# DIO.net
KiCad netlist of a schematic drawn in Altium Designer
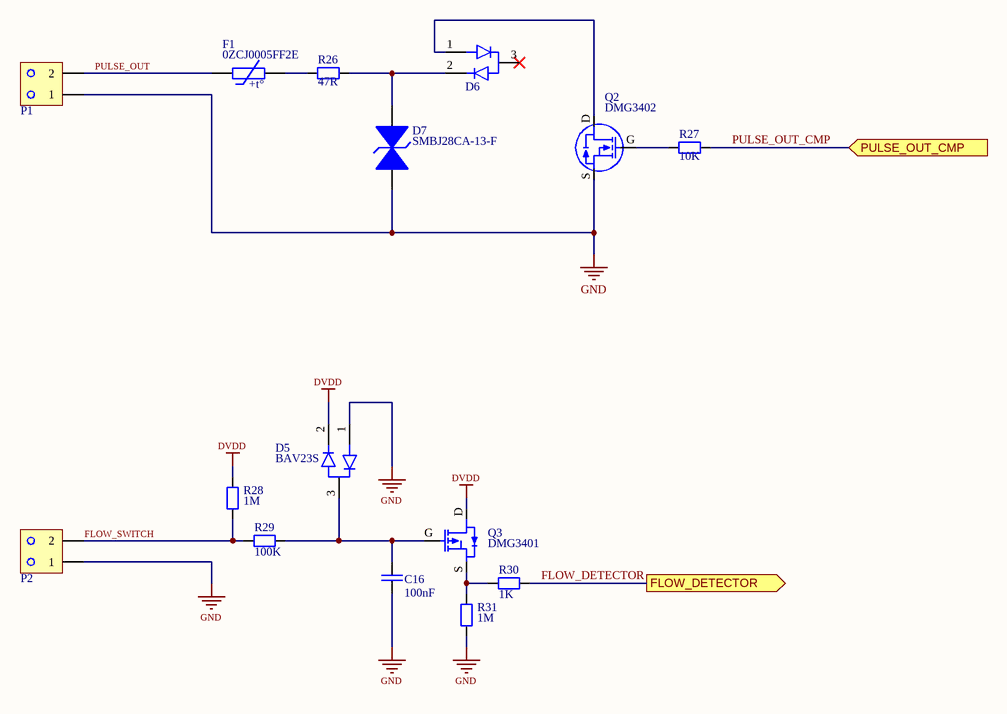
[diagram p0: DIO.SchDoc]

(export (version "E")
  (design (tool "Eeschema 10.0.6"))
  (components
    (comp (ref "C16")
      (value "100nF")
      (footprint "CAP_SM0805_YAGEOCC2_N")
      (description "CAP 100nF SM0805 X7R 25V YAGEO CC2")
      (fields
        (field (name "MANUFACTURER") "Yageo")
        (field (name "MANUFACTURER PART NUMBER") "CC0805KRX7R8BB104")
      )
      (libsource (lib "Yageo") (part "CC0805KRX7R8BB104"))
    )
    (comp (ref "D5")
      (value "BAV23S")
      (footprint "BAV23S")
      (description "DIODE ARRAY GP 250V 200MA SOT23")
      (fields (field (name "MANUFACTURER") "onsemi"))
      (libsource (lib "diode") (part "BAV23S"))
    )
    (comp (ref "D6")
      (value "BAV23S")
      (footprint "BAV23S")
      (description "DIODE ARRAY GP 250V 200MA SOT23")
      (fields (field (name "MANUFACTURER") "onsemi"))
      (libsource (lib "diode") (part "BAV23S"))
    )
    (comp (ref "D7")
      (value "SMBJ28CA-13-F")
      (footprint "SMBJ28CA-13-F")
      (fields
        (field (name "MANUFACTURER") "Diodes Incorporated")
        (field (name "MANUFACTURER PART NUMBER") "SMBJ24CA")
      )
      (libsource (lib "diode") (part "SMBJ28CA-13-F"))
    )
    (comp (ref "F1")
      (value "0ZCJ0005FF2E")
      (footprint "0ZCJ0005FF2E")
      (description "PTC RESET FUSE 60V 50MA 1206")
      (fields (field (name "MANUFACTURER") "Bel Fuse Inc."))
      (libsource (lib "fuse") (part "0ZCJ0005FF2E"))
    )
    (comp (ref "P1")
      (value "WJ15EDGVC-3.81-2P")
      (footprint "HEADER PLUG 2")
      (description "TERM BLOK FEMALE 1X2 3.81MM")
      (fields (field (name "MANUFACTURER") "Ningbo Kangnex Elec"))
      (libsource (lib "plug") (part "WJ15EDGVC-3.81-2P"))
    )
    (comp (ref "P2")
      (value "WJ15EDGVC-3.81-2P")
      (footprint "HEADER PLUG 2")
      (description "TERM BLOK FEMALE 1X2 3.81MM")
      (fields (field (name "MANUFACTURER") "Ningbo Kangnex Elec"))
      (libsource (lib "plug") (part "WJ15EDGVC-3.81-2P"))
    )
    (comp (ref "Q2")
      (value "DMG3402")
      (footprint "DMG3402L-7")
      (description "N-CHANNEL ENHANCEMENT MODE FIELD EFFECT TRANSISTOR\r\n85mΩ @ VGS = 2.5V -> ID 2A\r\nV(BR)DDS 30V")
      (fields
        (field (name "MANUFACTURER") "Diodes Incorporated")
        (field (name "MANUFACTURER PART NUMBER") "DMG3402L-7")
      )
      (libsource (lib "mosfet") (part "DMG3402L-7"))
    )
    (comp (ref "Q3")
      (value "DMG3401")
      (footprint "DMG3401LSN-7")
      (description "P-CHANNEL ENHANCEMENT MODE MOSFET\r\nRDS(ON) = 85mΩ @ VGS = -2.5V -> ID -2.7A\r\nV(BR)DDS 30V")
      (fields
        (field (name "MANUFACTURER") "Diodes Incorporated")
        (field (name "MANUFACTURER PART NUMBER") "DMG3401LSN-7")
      )
      (libsource (lib "mosfet") (part "DMG3401LSN-7"))
    )
    (comp (ref "R26")
      (value "47R")
      (footprint "RES_SM0805_YAGEORC_N")
      (description "RES 47R SM0805 YAGEO RC_L")
      (fields
        (field (name "MANUFACTURER") "Yageo")
        (field (name "MANUFACTURER PART NUMBER") "RC0805FR-0747RL")
      )
      (libsource (lib "Yageo") (part "RC0805FR-0747RL"))
    )
    (comp (ref "R27")
      (value "10K")
      (footprint "RES_SM0805_YAGEORC_N")
      (description "RES 10K SM0805 YAGEO RC_L")
      (fields
        (field (name "MANUFACTURER") "Yageo")
        (field (name "MANUFACTURER PART NUMBER") "RC0805FR-0710KL")
      )
      (libsource (lib "Yageo") (part "RC0805FR-0710KL"))
    )
    (comp (ref "R28")
      (value "1M")
      (footprint "RES_SM0805_YAGEORC_N")
      (description "RES 1M SM0805 YAGEO RC_L")
      (fields
        (field (name "MANUFACTURER") "Yageo")
        (field (name "MANUFACTURER PART NUMBER") "RC0805FR-071ML")
      )
      (libsource (lib "Yageo") (part "RC0805FR-071ML"))
    )
    (comp (ref "R29")
      (value "100K")
      (footprint "RES_SM0805_YAGEORC_N")
      (description "RES 100K SM0805 YAGEO RC_L")
      (fields
        (field (name "MANUFACTURER") "Yageo")
        (field (name "MANUFACTURER PART NUMBER") "RC0805FR-07100KL")
      )
      (libsource (lib "Yageo") (part "RC0805FR-07100KL"))
    )
    (comp (ref "R30")
      (value "1K")
      (footprint "RES_SM0805_YAGEORC_N")
      (description "RES 1K SM0805 YAGEO RC_L")
      (fields
        (field (name "MANUFACTURER") "Yageo")
        (field (name "MANUFACTURER PART NUMBER") "RC0805FR-071KL")
      )
      (libsource (lib "Yageo") (part "RC0805FR-071KL"))
    )
    (comp (ref "R31")
      (value "1M")
      (footprint "RES_SM0805_YAGEORC_N")
      (description "RES 1M SM0805 YAGEO RC_L")
      (fields
        (field (name "MANUFACTURER") "Yageo")
        (field (name "MANUFACTURER PART NUMBER") "RC0805FR-071ML")
      )
      (libsource (lib "Yageo") (part "RC0805FR-071ML"))
    )
  )
  (nets
    (net (code "1") (name "/FLOW_DETECTOR") (class "Default")
      (node (ref "R30") (pin "2") (pintype "passive"))
    )
    (net (code "2") (name "/FLOW_SWITCH") (class "Default")
      (node (ref "P2") (pin "2") (pinfunction "2_2") (pintype "passive"))
      (node (ref "R28") (pin "1") (pintype "passive"))
      (node (ref "R29") (pin "1") (pintype "passive"))
    )
    (net (code "3") (name "/PULSE_OUT") (class "Default")
      (node (ref "F1") (pin "1") (pinfunction "1_1") (pintype "passive"))
      (node (ref "P1") (pin "2") (pinfunction "2_2") (pintype "passive"))
    )
    (net (code "4") (name "/PULSE_OUT_CMP") (class "Default")
      (node (ref "R27") (pin "1") (pintype "passive"))
    )
    (net (code "5") (name "DVDD") (class "Default")
      (node (ref "D5") (pin "2") (pinfunction "2_2") (pintype "passive"))
      (node (ref "Q3") (pin "D") (pinfunction "D_D") (pintype "passive"))
      (node (ref "R28") (pin "2") (pintype "passive"))
    )
    (net (code "6") (name "GND") (class "Default")
      (node (ref "C16") (pin "2") (pintype "passive"))
      (node (ref "D5") (pin "1") (pinfunction "1_1") (pintype "passive"))
      (node (ref "D7") (pin "A") (pinfunction "A_A") (pintype "passive"))
      (node (ref "P1") (pin "1") (pinfunction "1_1") (pintype "passive"))
      (node (ref "P2") (pin "1") (pinfunction "1_1") (pintype "passive"))
      (node (ref "Q2") (pin "S") (pinfunction "S_S") (pintype "passive"))
      (node (ref "R31") (pin "1") (pintype "passive"))
    )
    (net (code "7") (name "Net-(C16-Pad1)") (class "Default")
      (node (ref "C16") (pin "1") (pintype "passive"))
      (node (ref "D5") (pin "3") (pinfunction "3_3") (pintype "passive"))
      (node (ref "Q3") (pin "G") (pinfunction "G_G") (pintype "passive"))
      (node (ref "R29") (pin "2") (pintype "passive"))
    )
    (net (code "8") (name "Net-(D6-Pad1)") (class "Default")
      (node (ref "D6") (pin "1") (pinfunction "1_1") (pintype "passive"))
      (node (ref "Q2") (pin "D") (pinfunction "D_D") (pintype "passive"))
    )
    (net (code "9") (name "Net-(D6-Pad2)") (class "Default")
      (node (ref "D6") (pin "2") (pinfunction "2_2") (pintype "passive"))
      (node (ref "D7") (pin "K") (pinfunction "K_K") (pintype "passive"))
      (node (ref "R26") (pin "1") (pintype "passive"))
    )
    (net (code "10") (name "Net-(F1-Pad2)") (class "Default")
      (node (ref "F1") (pin "2") (pinfunction "2_2") (pintype "passive"))
      (node (ref "R26") (pin "2") (pintype "passive"))
    )
    (net (code "11") (name "Net-(Q2-PadG)") (class "Default")
      (node (ref "Q2") (pin "G") (pinfunction "G_G") (pintype "passive"))
      (node (ref "R27") (pin "2") (pintype "passive"))
    )
    (net (code "12") (name "Net-(Q3-PadS)") (class "Default")
      (node (ref "Q3") (pin "S") (pinfunction "S_S") (pintype "passive"))
      (node (ref "R30") (pin "1") (pintype "passive"))
      (node (ref "R31") (pin "2") (pintype "passive"))
    )
    (net (code "13") (name "unconnected-(D6-Pad3)") (class "Default")
      (node (ref "D6") (pin "3") (pinfunction "3_3") (pintype "passive+no_connect"))
    )
  )
)
